# ECG_Circuit.net
KiCad netlist of a schematic drawn in EAGLE
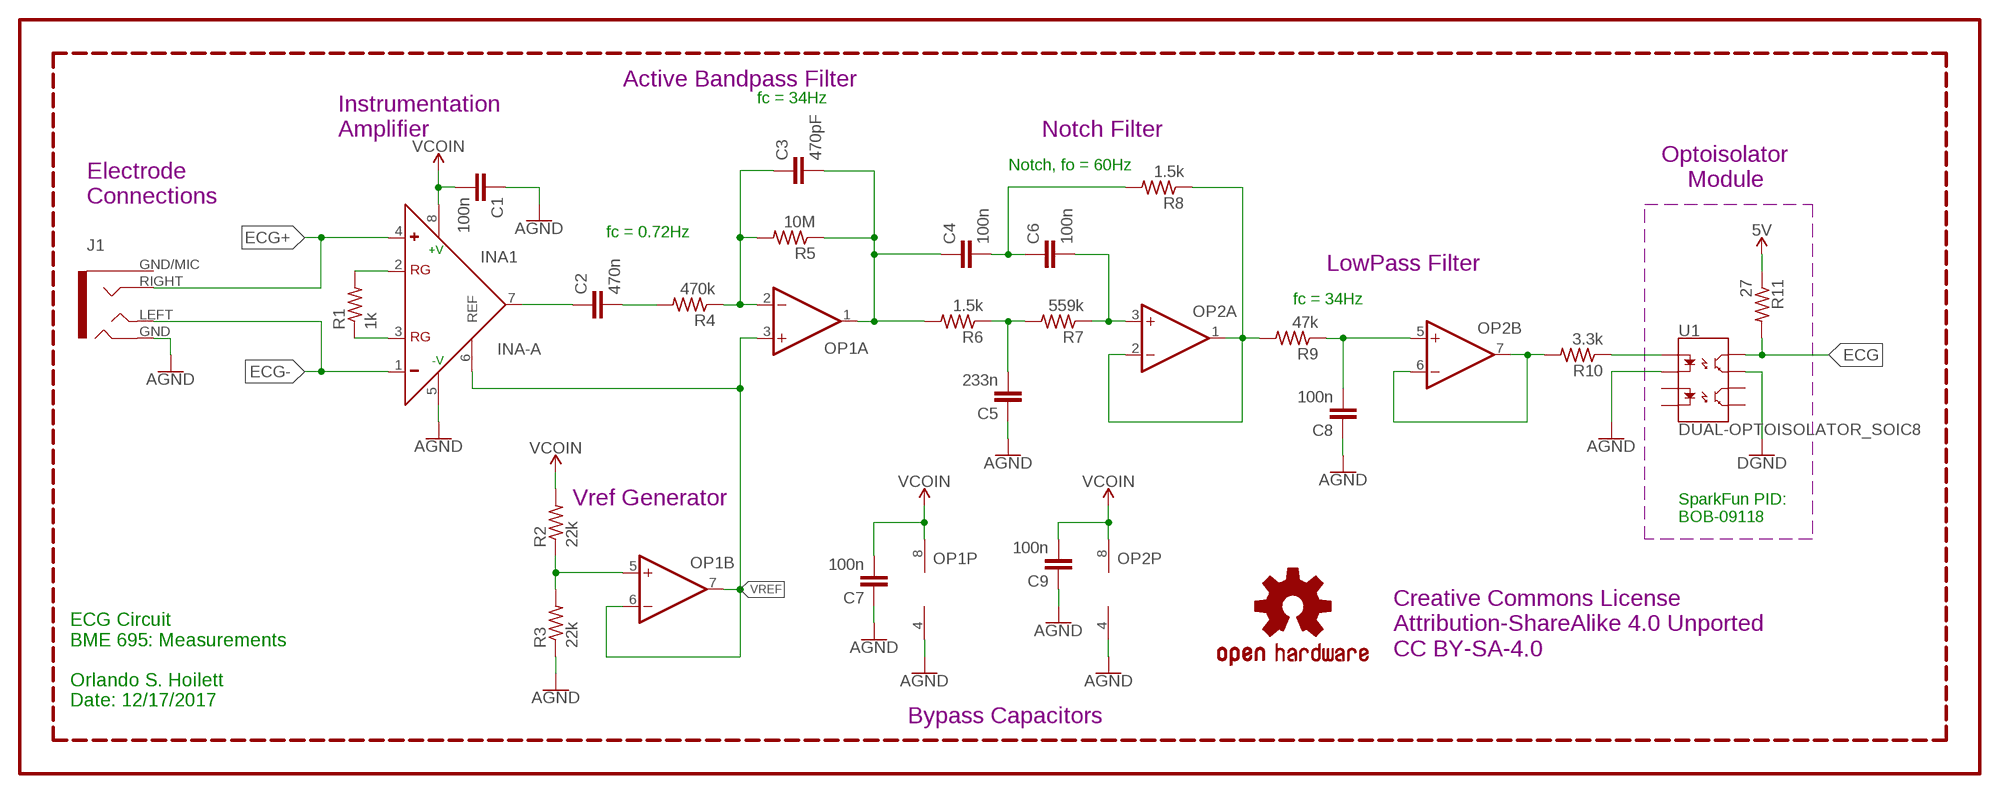
[diagram p0: schematic, sheet 1]

(export (version "E")
  (design (tool "Eeschema 10.0.6"))
  (components
    (comp (ref "C1")
      (value "100n")
      (footprint "eagle-import:C0402")
      (libsource (lib "eagle-import") (part "CAPACITOR0402"))
    )
    (comp (ref "C2")
      (value "470n")
      (footprint "eagle-import:C0402")
      (libsource (lib "eagle-import") (part "CAPACITOR0402"))
    )
    (comp (ref "C3")
      (value "470pF")
      (footprint "eagle-import:C0402")
      (libsource (lib "eagle-import") (part "CAPACITOR0402"))
    )
    (comp (ref "C4")
      (value "100n")
      (footprint "eagle-import:C0402")
      (libsource (lib "eagle-import") (part "CAPACITOR0402"))
    )
    (comp (ref "C5")
      (value "233n")
      (footprint "eagle-import:C0402")
      (libsource (lib "eagle-import") (part "CAPACITOR0402"))
    )
    (comp (ref "C6")
      (value "100n")
      (footprint "eagle-import:C0402")
      (libsource (lib "eagle-import") (part "CAPACITOR0402"))
    )
    (comp (ref "C7")
      (value "100n")
      (footprint "eagle-import:C0402")
      (libsource (lib "eagle-import") (part "CAPACITOR0402"))
    )
    (comp (ref "C8")
      (value "100n")
      (footprint "eagle-import:C0402")
      (libsource (lib "eagle-import") (part "CAPACITOR0402"))
    )
    (comp (ref "C9")
      (value "100n")
      (footprint "eagle-import:C0402")
      (libsource (lib "eagle-import") (part "CAPACITOR0402"))
    )
    (comp (ref "INA1")
      (value "INA-A")
      (footprint "eagle-import:MSOP08")
      (libsource (lib "eagle-import") (part "INA-A"))
    )
    (comp (ref "J1")
      (value "AUDIO_JACK_TRRSSMD_RA")
      (footprint "eagle-import:AUDIO_JACK_3.5MM_TRRS_SMD_RA")
      (libsource (lib "eagle-import") (part "AUDIO_JACK_TRRSSMD_RA"))
    )
    (comp (ref "LOGO1")
      (value "OSHW-LOGOS")
      (footprint "eagle-import:OSHW-LOGO-S")
      (libsource (lib "eagle-import") (part "OSHW-LOGOS"))
    )
    (comp (ref "OP1")
      (value "OP-DUALRM")
      (footprint "eagle-import:MSOP08")
      (fields (field (name "MF") "ALTERA CORPORATION") (field (name "MPN") "AD8607ARMZ-REEL"))
      (libsource (lib "eagle-import") (part "OP-DUALRM"))
    )
    (comp (ref "OP2")
      (value "OP-DUALRM")
      (footprint "eagle-import:MSOP08")
      (fields (field (name "MF") "ALTERA CORPORATION") (field (name "MPN") "AD8607ARMZ-REEL"))
      (libsource (lib "eagle-import") (part "OP-DUALRM"))
    )
    (comp (ref "R1")
      (value "1k")
      (footprint "eagle-import:R0402")
      (libsource (lib "eagle-import") (part "RESISTOR0402"))
    )
    (comp (ref "R2")
      (value "22k")
      (footprint "eagle-import:R0402")
      (libsource (lib "eagle-import") (part "RESISTOR0402"))
    )
    (comp (ref "R3")
      (value "22k")
      (footprint "eagle-import:R0402")
      (libsource (lib "eagle-import") (part "RESISTOR0402"))
    )
    (comp (ref "R4")
      (value "470k")
      (footprint "eagle-import:R0402")
      (libsource (lib "eagle-import") (part "RESISTOR0402"))
    )
    (comp (ref "R5")
      (value "10M")
      (footprint "eagle-import:R0402")
      (libsource (lib "eagle-import") (part "RESISTOR0402"))
    )
    (comp (ref "R6")
      (value "1.5k")
      (footprint "eagle-import:R0402")
      (libsource (lib "eagle-import") (part "RESISTOR0402"))
    )
    (comp (ref "R7")
      (value "559k")
      (footprint "eagle-import:R0402")
      (libsource (lib "eagle-import") (part "RESISTOR0402"))
    )
    (comp (ref "R8")
      (value "1.5k")
      (footprint "eagle-import:R0402")
      (libsource (lib "eagle-import") (part "RESISTOR0402"))
    )
    (comp (ref "R9")
      (value "47k")
      (footprint "eagle-import:R0402")
      (libsource (lib "eagle-import") (part "RESISTOR0402"))
    )
    (comp (ref "R10")
      (value "3.3k")
      (footprint "eagle-import:R0402")
      (libsource (lib "eagle-import") (part "RESISTOR0402"))
    )
    (comp (ref "R11")
      (value "27")
      (footprint "eagle-import:R0402")
      (libsource (lib "eagle-import") (part "RESISTOR0402"))
    )
    (comp (ref "U1")
      (value "DUAL-OPTOISOLATOR_SOIC8")
      (footprint "eagle-import:SO08")
      (libsource (lib "eagle-import") (part "DUAL-OPTOISOLATOR_SOIC8"))
    )
  )
  (nets
    (net (code "1") (name "5V") (class "Default")
      (node (ref "R11") (pin "1") (pinfunction "1_1") (pintype "passive"))
    )
    (net (code "2") (name "AGND") (class "Default")
      (node (ref "C1") (pin "1") (pinfunction "1_1") (pintype "passive"))
      (node (ref "C5") (pin "1") (pinfunction "1_1") (pintype "passive"))
      (node (ref "C7") (pin "1") (pinfunction "1_1") (pintype "passive"))
      (node (ref "C8") (pin "1") (pinfunction "1_1") (pintype "passive"))
      (node (ref "C9") (pin "1") (pinfunction "1_1") (pintype "passive"))
      (node (ref "INA1") (pin "5") (pinfunction "-V_5") (pintype "power_in"))
      (node (ref "J1") (pin "GND") (pinfunction "RING2_GND") (pintype "bidirectional"))
      (node (ref "OP1") (pin "4") (pinfunction "V-_4") (pintype "power_in"))
      (node (ref "OP2") (pin "4") (pinfunction "V-_4") (pintype "power_in"))
      (node (ref "R3") (pin "1") (pinfunction "1_1") (pintype "passive"))
      (node (ref "U1") (pin "2") (pinfunction "C1_2") (pintype "bidirectional"))
    )
    (net (code "3") (name "DGND") (class "Default")
      (node (ref "U1") (pin "7") (pinfunction "EM1_7") (pintype "bidirectional"))
    )
    (net (code "4") (name "ECG") (class "Default")
      (node (ref "OP2") (pin "6") (pinfunction "-IN_6") (pintype "input"))
      (node (ref "OP2") (pin "7") (pinfunction "OUT_7") (pintype "output"))
      (node (ref "R10") (pin "2") (pinfunction "2_2") (pintype "passive"))
      (node (ref "R11") (pin "2") (pinfunction "2_2") (pintype "passive"))
      (node (ref "U1") (pin "8") (pinfunction "CL1_8") (pintype "bidirectional"))
    )
    (net (code "5") (name "ECG+") (class "Default")
      (node (ref "INA1") (pin "4") (pinfunction "IN+_4") (pintype "input"))
      (node (ref "J1") (pin "RIGHT") (pinfunction "RING1_RIGHT") (pintype "bidirectional"))
    )
    (net (code "6") (name "ECG-") (class "Default")
      (node (ref "INA1") (pin "1") (pinfunction "IN-_1") (pintype "input"))
      (node (ref "J1") (pin "LEFT") (pinfunction "TIP_LEFT") (pintype "bidirectional"))
    )
    (net (code "7") (name "Net-(C2-Pad2)") (class "Default")
      (node (ref "C2") (pin "2") (pinfunction "2_2") (pintype "passive"))
      (node (ref "R4") (pin "2") (pinfunction "2_2") (pintype "passive"))
    )
    (net (code "8") (name "Net-(C4-Pad2)") (class "Default")
      (node (ref "C4") (pin "2") (pinfunction "2_2") (pintype "passive"))
      (node (ref "C6") (pin "1") (pinfunction "1_1") (pintype "passive"))
      (node (ref "R8") (pin "2") (pinfunction "2_2") (pintype "passive"))
    )
    (net (code "9") (name "Net-(C5-Pad2)") (class "Default")
      (node (ref "C5") (pin "2") (pinfunction "2_2") (pintype "passive"))
      (node (ref "R6") (pin "1") (pinfunction "1_1") (pintype "passive"))
      (node (ref "R7") (pin "2") (pinfunction "2_2") (pintype "passive"))
    )
    (net (code "10") (name "Net-(INA1-OUT)") (class "Default")
      (node (ref "C2") (pin "1") (pinfunction "1_1") (pintype "passive"))
      (node (ref "INA1") (pin "7") (pinfunction "OUT_7") (pintype "output"))
    )
    (net (code "11") (name "Net-(INA1-RG-Pad2)") (class "Default")
      (node (ref "INA1") (pin "2") (pinfunction "RG_2") (pintype "passive"))
      (node (ref "R1") (pin "2") (pinfunction "2_2") (pintype "passive"))
    )
    (net (code "12") (name "Net-(INA1-RG-Pad3)") (class "Default")
      (node (ref "INA1") (pin "3") (pinfunction "RG_3") (pintype "passive"))
      (node (ref "R1") (pin "1") (pinfunction "1_1") (pintype "passive"))
    )
    (net (code "13") (name "Net-(OP1A--IN)") (class "Default")
      (node (ref "C3") (pin "1") (pinfunction "1_1") (pintype "passive"))
      (node (ref "OP1") (pin "2") (pinfunction "-IN_2") (pintype "input"))
      (node (ref "R4") (pin "1") (pinfunction "1_1") (pintype "passive"))
      (node (ref "R5") (pin "2") (pinfunction "2_2") (pintype "passive"))
    )
    (net (code "14") (name "Net-(OP1A-OUT)") (class "Default")
      (node (ref "C3") (pin "2") (pinfunction "2_2") (pintype "passive"))
      (node (ref "C4") (pin "1") (pinfunction "1_1") (pintype "passive"))
      (node (ref "OP1") (pin "1") (pinfunction "OUT_1") (pintype "output"))
      (node (ref "R5") (pin "1") (pinfunction "1_1") (pintype "passive"))
      (node (ref "R6") (pin "2") (pinfunction "2_2") (pintype "passive"))
    )
    (net (code "15") (name "Net-(OP1B-+IN)") (class "Default")
      (node (ref "OP1") (pin "5") (pinfunction "+IN_5") (pintype "input"))
      (node (ref "R2") (pin "1") (pinfunction "1_1") (pintype "passive"))
      (node (ref "R3") (pin "2") (pinfunction "2_2") (pintype "passive"))
    )
    (net (code "16") (name "Net-(OP2A-+IN)") (class "Default")
      (node (ref "C6") (pin "2") (pinfunction "2_2") (pintype "passive"))
      (node (ref "OP2") (pin "3") (pinfunction "+IN_3") (pintype "input"))
      (node (ref "R7") (pin "1") (pinfunction "1_1") (pintype "passive"))
    )
    (net (code "17") (name "Net-(OP2A--IN)") (class "Default")
      (node (ref "OP2") (pin "1") (pinfunction "OUT_1") (pintype "output"))
      (node (ref "OP2") (pin "2") (pinfunction "-IN_2") (pintype "input"))
      (node (ref "R8") (pin "1") (pinfunction "1_1") (pintype "passive"))
      (node (ref "R9") (pin "2") (pinfunction "2_2") (pintype "passive"))
    )
    (net (code "18") (name "Net-(OP2B-+IN)") (class "Default")
      (node (ref "C8") (pin "2") (pinfunction "2_2") (pintype "passive"))
      (node (ref "OP2") (pin "5") (pinfunction "+IN_5") (pintype "input"))
      (node (ref "R9") (pin "1") (pinfunction "1_1") (pintype "passive"))
    )
    (net (code "19") (name "Net-(U1-A1)") (class "Default")
      (node (ref "R10") (pin "1") (pinfunction "1_1") (pintype "passive"))
      (node (ref "U1") (pin "1") (pinfunction "A1_1") (pintype "bidirectional"))
    )
    (net (code "20") (name "VCOIN") (class "Default")
      (node (ref "C1") (pin "2") (pinfunction "2_2") (pintype "passive"))
      (node (ref "C7") (pin "2") (pinfunction "2_2") (pintype "passive"))
      (node (ref "C9") (pin "2") (pinfunction "2_2") (pintype "passive"))
      (node (ref "INA1") (pin "8") (pinfunction "+V_8") (pintype "power_in"))
      (node (ref "OP1") (pin "8") (pinfunction "V+_8") (pintype "power_in"))
      (node (ref "OP2") (pin "8") (pinfunction "V+_8") (pintype "power_in"))
      (node (ref "R2") (pin "2") (pinfunction "2_2") (pintype "passive"))
    )
    (net (code "21") (name "VREF") (class "Default")
      (node (ref "INA1") (pin "6") (pinfunction "REF_6") (pintype "passive"))
      (node (ref "OP1") (pin "3") (pinfunction "+IN_3") (pintype "input"))
      (node (ref "OP1") (pin "6") (pinfunction "-IN_6") (pintype "input"))
      (node (ref "OP1") (pin "7") (pinfunction "OUT_7") (pintype "output"))
    )
    (net (code "22") (name "unconnected-(J1-SLEEVE-PadGND{slash}MIC)") (class "Default")
      (node (ref "J1") (pin "GND/MIC") (pinfunction "SLEEVE_GND/MIC") (pintype "bidirectional"))
    )
    (net (code "23") (name "unconnected-(U1-A2-Pad3)") (class "Default")
      (node (ref "U1") (pin "3") (pinfunction "A2_3") (pintype "bidirectional"))
    )
    (net (code "24") (name "unconnected-(U1-C2-Pad4)") (class "Default")
      (node (ref "U1") (pin "4") (pinfunction "C2_4") (pintype "bidirectional"))
    )
    (net (code "25") (name "unconnected-(U1-CL2-Pad6)") (class "Default")
      (node (ref "U1") (pin "6") (pinfunction "CL2_6") (pintype "bidirectional"))
    )
    (net (code "26") (name "unconnected-(U1-EM2-Pad5)") (class "Default")
      (node (ref "U1") (pin "5") (pinfunction "EM2_5") (pintype "bidirectional"))
    )
  )
)
